# SparkFun_Qwiic_Thermocouple_Amplifier_PC.net
KiCad netlist of a schematic drawn in EAGLE
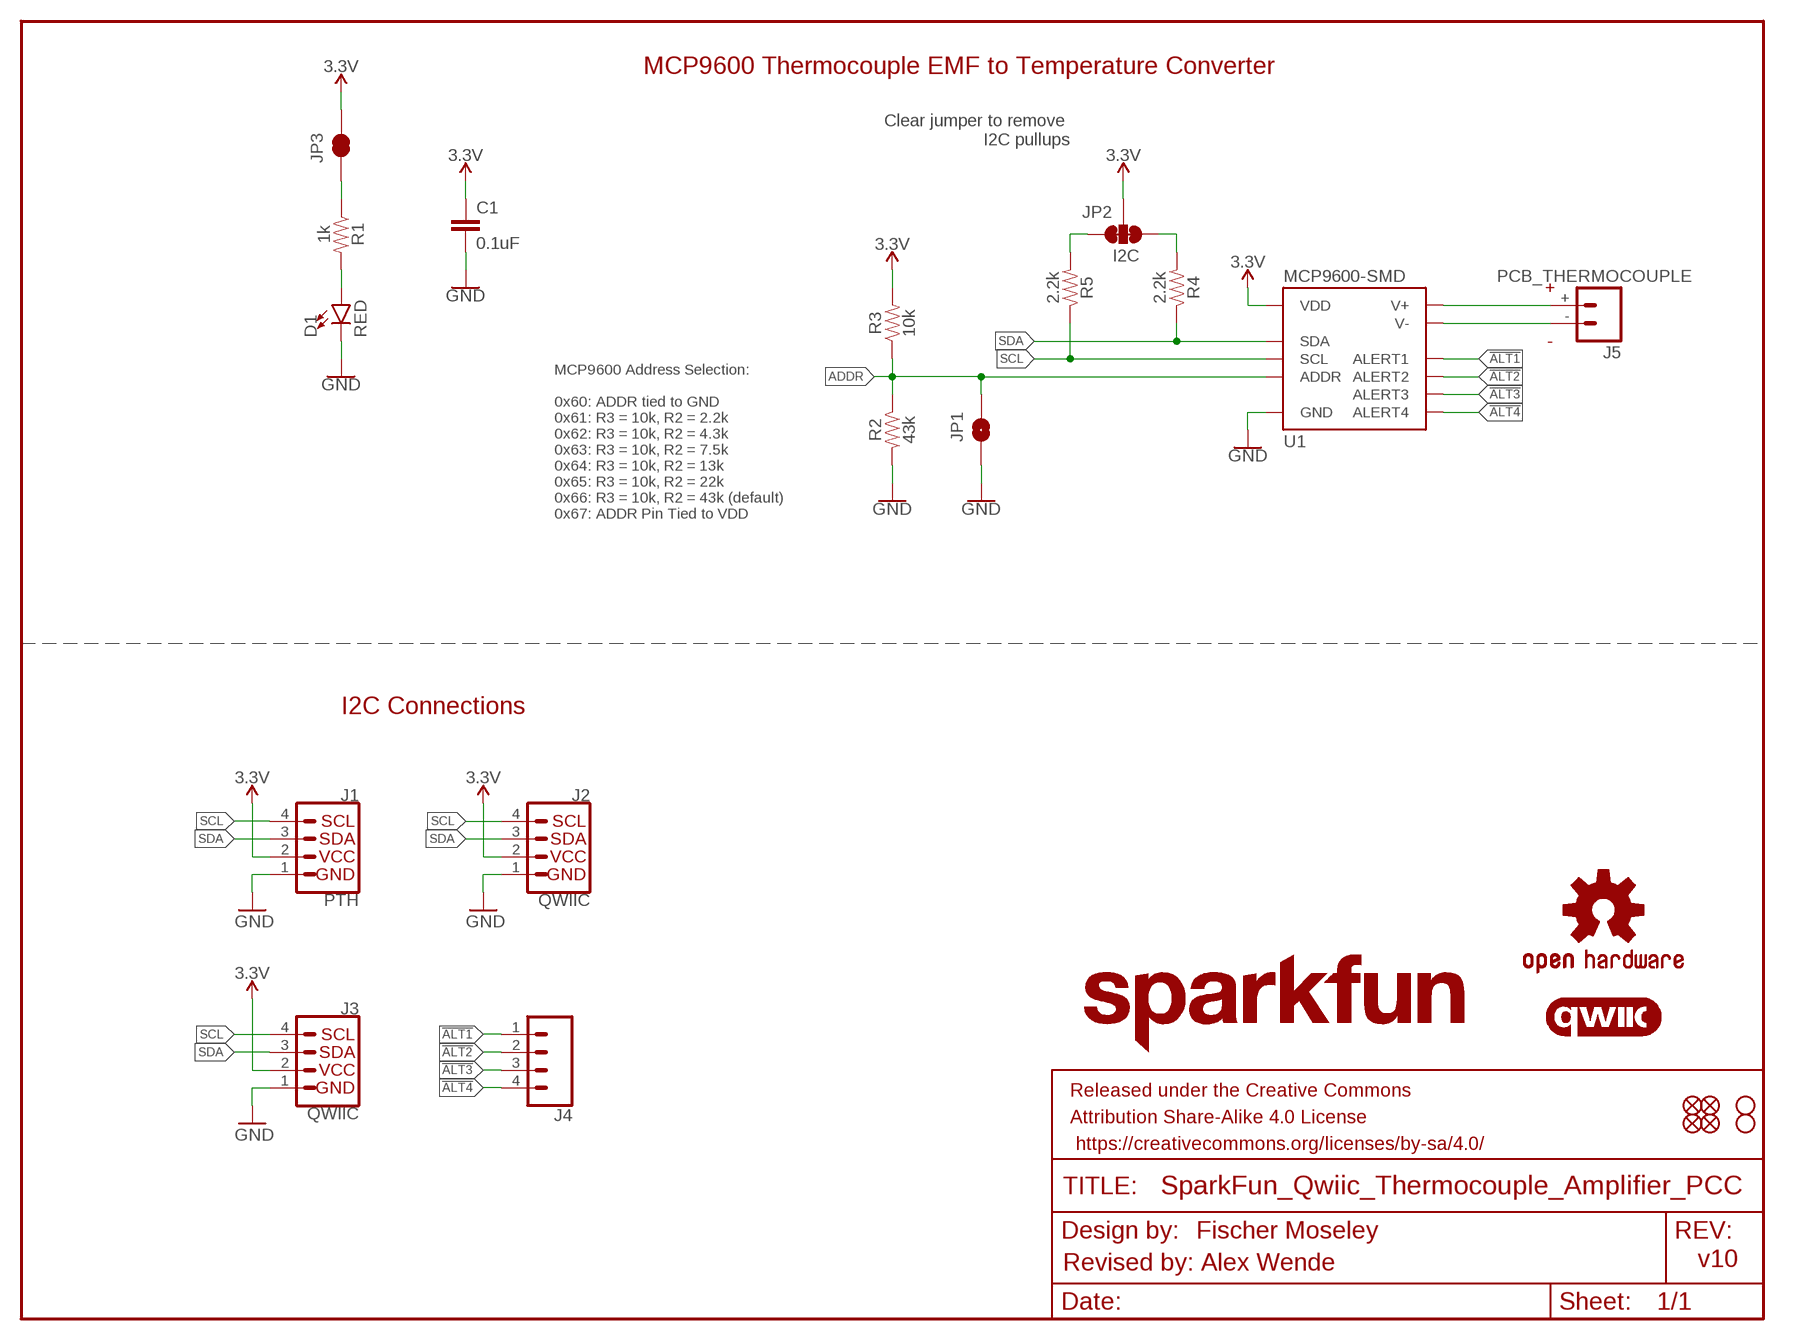
[diagram p0: schematic, sheet 1]

(export (version "E")
  (design (tool "Eeschema 10.0.6"))
  (components
    (comp (ref "C1")
      (value "0.1uF")
      (footprint "eagle-import:0603")
      (libsource (lib "eagle-import") (part "0.1UF-0603-25V-(+80/-20%)"))
    )
    (comp (ref "D1")
      (value "RED")
      (footprint "eagle-import:LED-0603")
      (libsource (lib "eagle-import") (part "LED-RED0603"))
    )
    (comp (ref "FD1")
      (value "FIDUCIAL1X2")
      (footprint "eagle-import:FIDUCIAL-1X2")
      (libsource (lib "eagle-import") (part "FIDUCIAL1X2"))
    )
    (comp (ref "FD2")
      (value "FIDUCIAL1X2")
      (footprint "eagle-import:FIDUCIAL-1X2")
      (libsource (lib "eagle-import") (part "FIDUCIAL1X2"))
    )
    (comp (ref "FD3")
      (value "FIDUCIAL1X2")
      (footprint "eagle-import:FIDUCIAL-1X2")
      (libsource (lib "eagle-import") (part "FIDUCIAL1X2"))
    )
    (comp (ref "FD4")
      (value "FIDUCIAL1X2")
      (footprint "eagle-import:FIDUCIAL-1X2")
      (libsource (lib "eagle-import") (part "FIDUCIAL1X2"))
    )
    (comp (ref "FRAME1")
      (value "FRAME-LETTER")
      (footprint "eagle-import:CREATIVE_COMMONS")
      (libsource (lib "eagle-import") (part "FRAME-LETTER"))
    )
    (comp (ref "J1")
      (value "PTH")
      (footprint "eagle-import:1X04_NO_SILK")
      (libsource (lib "eagle-import") (part "I2C_STANDARD_NO_SILK"))
    )
    (comp (ref "J2")
      (value "QWIIC")
      (footprint "eagle-import:JST04_1MM_RA")
      (libsource (lib "eagle-import") (part "QWIIC_CONNECTORJS-1MM"))
    )
    (comp (ref "J3")
      (value "QWIIC")
      (footprint "eagle-import:JST04_1MM_RA")
      (libsource (lib "eagle-import") (part "QWIIC_CONNECTORJS-1MM"))
    )
    (comp (ref "J4")
      (value "CONN_041X04_NO_SILK")
      (footprint "eagle-import:1X04_NO_SILK")
      (libsource (lib "eagle-import") (part "CONN_041X04_NO_SILK"))
    )
    (comp (ref "J5")
      (value "PCB_THERMOCOUPLE")
      (footprint "eagle-import:PCC-SMP")
      (libsource (lib "eagle-import") (part "PCB_THERMOCOUPLE"))
    )
    (comp (ref "JP1")
      (value "JUMPER-SMT_2_NO_SILK")
      (footprint "eagle-import:SMT-JUMPER_2_NO_SILK")
      (libsource (lib "eagle-import") (part "JUMPER-SMT_2_NO_SILK"))
    )
    (comp (ref "JP2")
      (value "I2C")
      (footprint "eagle-import:SMT-JUMPER_3_2-NC_TRACE_SILK")
      (libsource (lib "eagle-import") (part "JUMPER-SMT_3_2-NC_TRACE_SILK"))
    )
    (comp (ref "JP3")
      (value "JUMPER-SMT_2_NC_TRACE_SILK")
      (footprint "eagle-import:SMT-JUMPER_2_NC_TRACE_SILK")
      (libsource (lib "eagle-import") (part "JUMPER-SMT_2_NC_TRACE_SILK"))
    )
    (comp (ref "JP8")
      (value "STAND-OFF")
      (footprint "eagle-import:STAND-OFF")
      (libsource (lib "eagle-import") (part "STAND-OFF"))
    )
    (comp (ref "JP9")
      (value "STAND-OFF")
      (footprint "eagle-import:STAND-OFF")
      (libsource (lib "eagle-import") (part "STAND-OFF"))
    )
    (comp (ref "LOGO1")
      (value "OSHW-LOGOMINI")
      (footprint "eagle-import:OSHW-LOGO-MINI")
      (libsource (lib "eagle-import") (part "OSHW-LOGOMINI"))
    )
    (comp (ref "LOGO2")
      (value "SFE_LOGO_NAME.1_INCH")
      (footprint "eagle-import:SFE_LOGO_NAME_.1")
      (libsource (lib "eagle-import") (part "SFE_LOGO_NAME.1_INCH"))
    )
    (comp (ref "LOGO3")
      (value "QWIIC_LOGO_5MM")
      (footprint "eagle-import:QWIIC_5MM")
      (libsource (lib "eagle-import") (part "QWIIC_LOGO_5MM"))
    )
    (comp (ref "R1")
      (value "1k")
      (footprint "eagle-import:0603")
      (libsource (lib "eagle-import") (part "1KOHM-0603-1/10W-1%"))
    )
    (comp (ref "R2")
      (value "43k")
      (footprint "eagle-import:0603")
      (libsource (lib "eagle-import") (part "43KOHM-0603-1/10W-1%"))
    )
    (comp (ref "R3")
      (value "10k")
      (footprint "eagle-import:0603")
      (libsource (lib "eagle-import") (part "10KOHM-0603-1/10W-1%"))
    )
    (comp (ref "R4")
      (value "2.2k")
      (footprint "eagle-import:0603")
      (libsource (lib "eagle-import") (part "2.2KOHM-0603-1/10W-1%"))
    )
    (comp (ref "R5")
      (value "2.2k")
      (footprint "eagle-import:0603")
      (libsource (lib "eagle-import") (part "2.2KOHM-0603-1/10W-1%"))
    )
    (comp (ref "U1")
      (value "MCP9600-SMD")
      (footprint "eagle-import:MQFN-20")
      (libsource (lib "eagle-import") (part "MCP9600-SMD"))
    )
  )
  (nets
    (net (code "1") (name "/~{ALT1}") (class "Default")
      (node (ref "J4") (pin "1") (pinfunction "1_1") (pintype "passive"))
      (node (ref "U1") (pin "11") (pinfunction "ALERT1_11") (pintype "bidirectional"))
    )
    (net (code "2") (name "/~{ALT2}") (class "Default")
      (node (ref "J4") (pin "2") (pinfunction "2_2") (pintype "passive"))
      (node (ref "U1") (pin "12") (pinfunction "ALERT2_12") (pintype "bidirectional"))
    )
    (net (code "3") (name "/~{ALT3}") (class "Default")
      (node (ref "J4") (pin "3") (pinfunction "3_3") (pintype "passive"))
      (node (ref "U1") (pin "14") (pinfunction "ALERT3_14") (pintype "bidirectional"))
    )
    (net (code "4") (name "/~{ALT4}") (class "Default")
      (node (ref "J4") (pin "4") (pinfunction "4_4") (pintype "passive"))
      (node (ref "U1") (pin "15") (pinfunction "ALERT4_15") (pintype "bidirectional"))
    )
    (net (code "5") (name "3.3V") (class "Default")
      (node (ref "C1") (pin "1") (pinfunction "1_1") (pintype "passive"))
      (node (ref "J1") (pin "2") (pinfunction "2_2") (pintype "power_in"))
      (node (ref "J2") (pin "2") (pinfunction "2_2") (pintype "power_in"))
      (node (ref "J3") (pin "2") (pinfunction "2_2") (pintype "power_in"))
      (node (ref "JP2") (pin "2") (pinfunction "2_2") (pintype "passive"))
      (node (ref "JP3") (pin "2") (pinfunction "2_2") (pintype "passive"))
      (node (ref "R3") (pin "2") (pinfunction "2_2") (pintype "passive"))
      (node (ref "U1") (pin "8") (pinfunction "VDD_8") (pintype "bidirectional"))
    )
    (net (code "6") (name "ADDR") (class "Default")
      (node (ref "JP1") (pin "1") (pinfunction "1_1") (pintype "passive"))
      (node (ref "R2") (pin "1") (pinfunction "1_1") (pintype "passive"))
      (node (ref "R3") (pin "1") (pinfunction "1_1") (pintype "passive"))
      (node (ref "U1") (pin "16") (pinfunction "ADDR_16") (pintype "bidirectional"))
    )
    (net (code "7") (name "GND") (class "Default")
      (node (ref "C1") (pin "2") (pinfunction "2_2") (pintype "passive"))
      (node (ref "D1") (pin "C") (pinfunction "C_C") (pintype "passive"))
      (node (ref "J1") (pin "1") (pinfunction "1_1") (pintype "power_in"))
      (node (ref "J2") (pin "1") (pinfunction "1_1") (pintype "power_in"))
      (node (ref "J3") (pin "1") (pinfunction "1_1") (pintype "power_in"))
      (node (ref "JP1") (pin "2") (pinfunction "2_2") (pintype "passive"))
      (node (ref "R2") (pin "2") (pinfunction "2_2") (pintype "passive"))
      (node (ref "U1") (pin "1") (pinfunction "GND_1") (pintype "bidirectional"))
      (node (ref "U1") (pin "10") (pinfunction "GND_10") (pintype "bidirectional"))
      (node (ref "U1") (pin "13") (pinfunction "GND_13") (pintype "bidirectional"))
      (node (ref "U1") (pin "17") (pinfunction "GND_17") (pintype "bidirectional"))
      (node (ref "U1") (pin "18") (pinfunction "GND_18") (pintype "bidirectional"))
      (node (ref "U1") (pin "21") (pinfunction "GND_21") (pintype "bidirectional"))
      (node (ref "U1") (pin "3") (pinfunction "GND_3") (pintype "bidirectional"))
      (node (ref "U1") (pin "5") (pinfunction "GND_5") (pintype "bidirectional"))
      (node (ref "U1") (pin "6") (pinfunction "GND_6") (pintype "bidirectional"))
      (node (ref "U1") (pin "7") (pinfunction "GND_7") (pintype "bidirectional"))
      (node (ref "U1") (pin "9") (pinfunction "GND_9") (pintype "bidirectional"))
    )
    (net (code "8") (name "Net-(D1-PadA)") (class "Default")
      (node (ref "D1") (pin "A") (pinfunction "A_A") (pintype "passive"))
      (node (ref "R1") (pin "2") (pinfunction "2_2") (pintype "passive"))
    )
    (net (code "9") (name "Net-(JP2-Pad1)") (class "Default")
      (node (ref "JP2") (pin "1") (pinfunction "1_1") (pintype "passive"))
      (node (ref "R5") (pin "2") (pinfunction "2_2") (pintype "passive"))
    )
    (net (code "10") (name "Net-(JP2-Pad3)") (class "Default")
      (node (ref "JP2") (pin "3") (pinfunction "3_3") (pintype "passive"))
      (node (ref "R4") (pin "2") (pinfunction "2_2") (pintype "passive"))
    )
    (net (code "11") (name "Net-(JP3-Pad1)") (class "Default")
      (node (ref "JP3") (pin "1") (pinfunction "1_1") (pintype "passive"))
      (node (ref "R1") (pin "1") (pinfunction "1_1") (pintype "passive"))
    )
    (net (code "12") (name "Net-(U1-V+)") (class "Default")
      (node (ref "J5") (pin "+") (pinfunction "+_+") (pintype "passive"))
      (node (ref "U1") (pin "2") (pinfunction "V+_2") (pintype "bidirectional"))
    )
    (net (code "13") (name "Net-(U1-V-)") (class "Default")
      (node (ref "J5") (pin "-") (pinfunction "-_-") (pintype "passive"))
      (node (ref "U1") (pin "4") (pinfunction "V-_4") (pintype "bidirectional"))
    )
    (net (code "14") (name "SCL") (class "Default")
      (node (ref "J1") (pin "4") (pinfunction "4_4") (pintype "passive"))
      (node (ref "J2") (pin "4") (pinfunction "4_4") (pintype "passive"))
      (node (ref "J3") (pin "4") (pinfunction "4_4") (pintype "passive"))
      (node (ref "R5") (pin "1") (pinfunction "1_1") (pintype "passive"))
      (node (ref "U1") (pin "19") (pinfunction "SCL_19") (pintype "bidirectional"))
    )
    (net (code "15") (name "SDA") (class "Default")
      (node (ref "J1") (pin "3") (pinfunction "3_3") (pintype "passive"))
      (node (ref "J2") (pin "3") (pinfunction "3_3") (pintype "passive"))
      (node (ref "J3") (pin "3") (pinfunction "3_3") (pintype "passive"))
      (node (ref "R4") (pin "1") (pinfunction "1_1") (pintype "passive"))
      (node (ref "U1") (pin "20") (pinfunction "SDA_20") (pintype "bidirectional"))
    )
  )
)
